# led_stripe_pwm.net
KiCad netlist of a schematic drawn in EAGLE
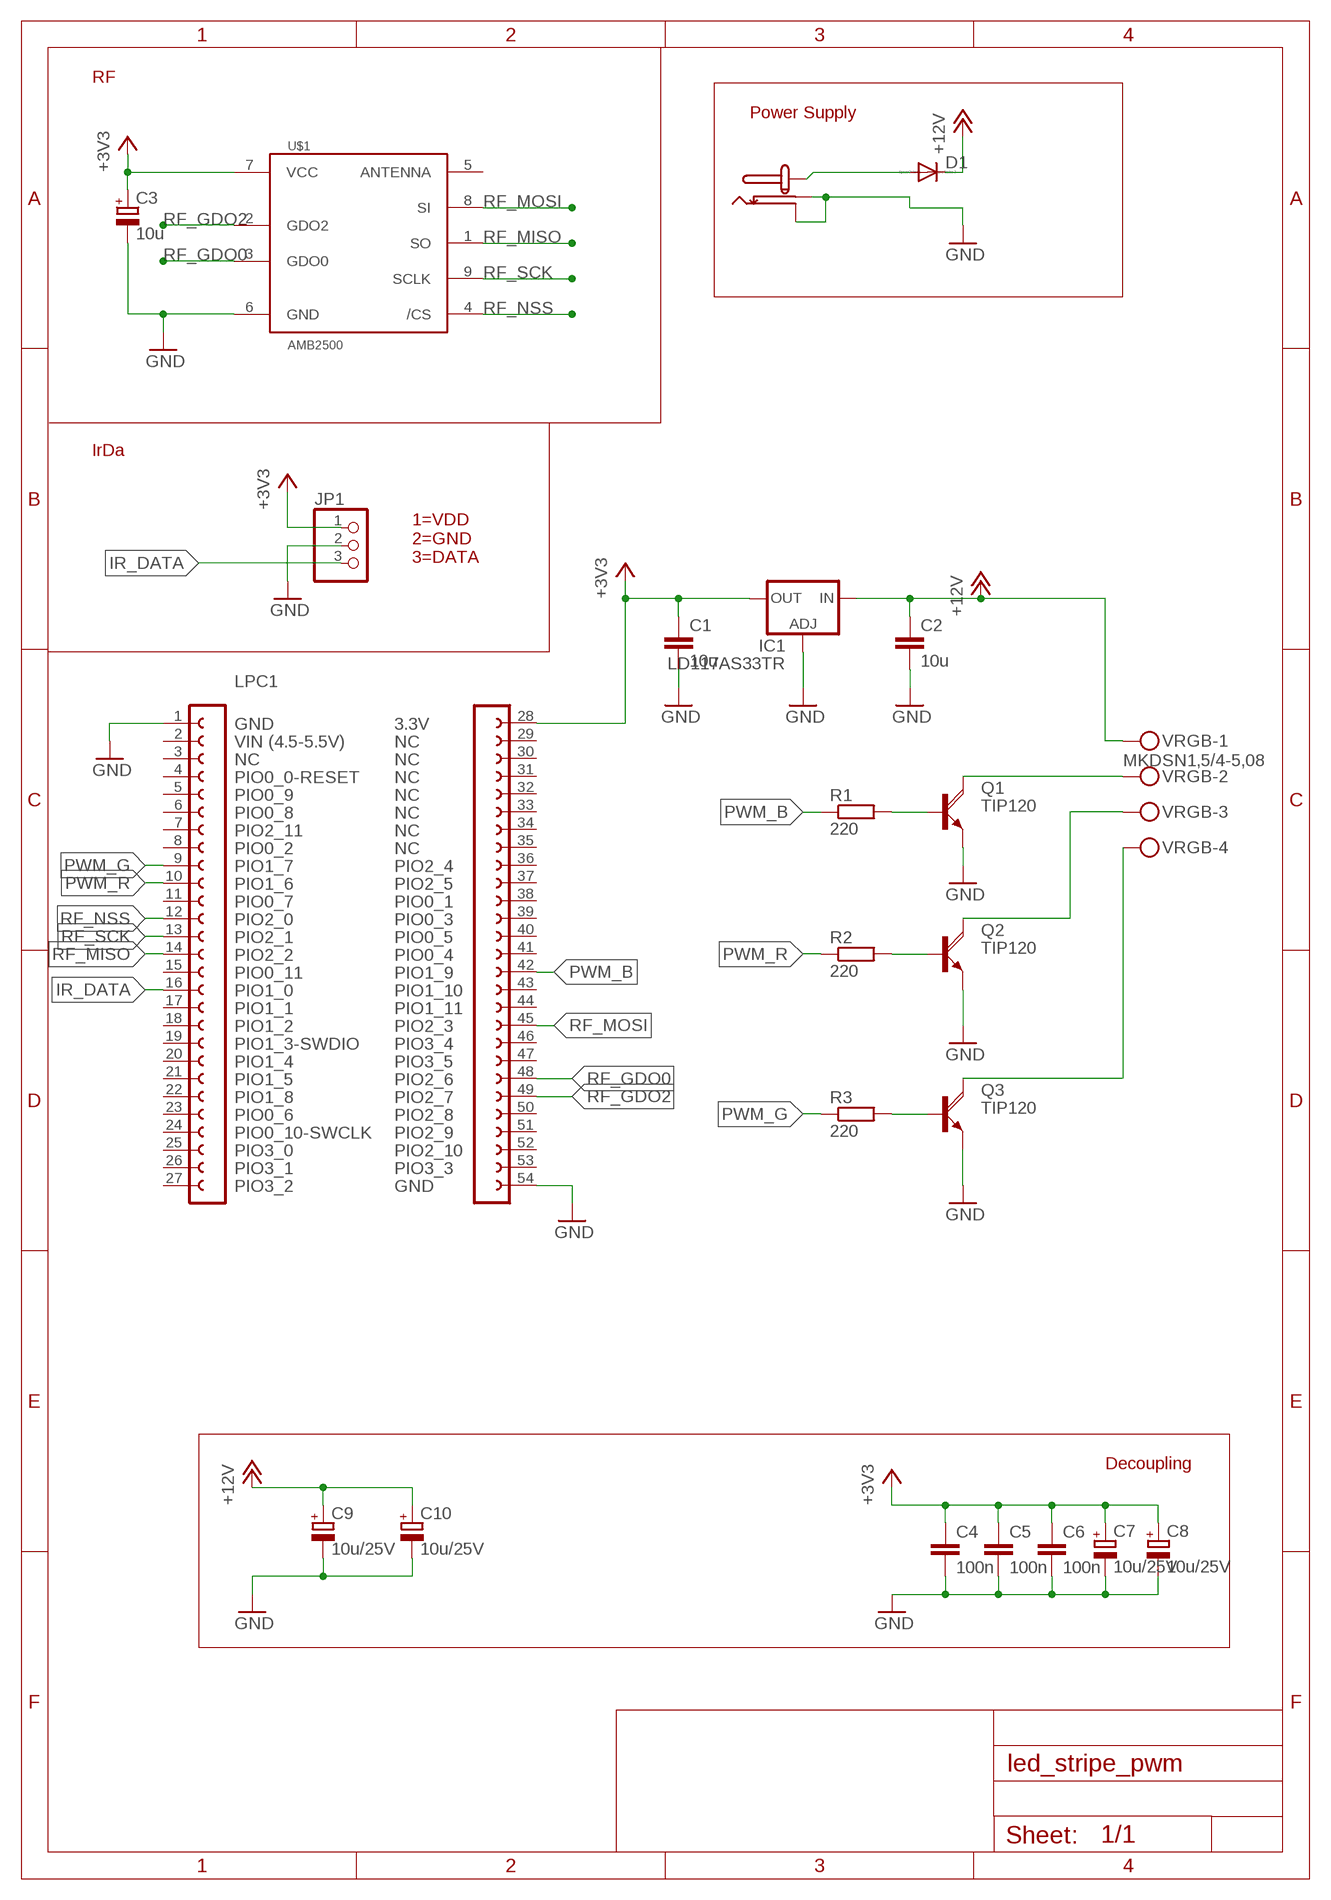
[diagram p0: schematic, sheet 1]

(export (version "E")
  (design (tool "Eeschema 10.0.6"))
  (components
    (comp (ref "C1")
      (value "10u")
      (footprint "eagle-import:C0805K")
      (libsource (lib "eagle-import") (part "C-EUC0805K"))
    )
    (comp (ref "C2")
      (value "10u")
      (footprint "eagle-import:C0805K")
      (libsource (lib "eagle-import") (part "C-EUC0805K"))
    )
    (comp (ref "C3")
      (value "10u")
      (footprint "eagle-import:A_3216-18W")
      (libsource (lib "eagle-import") (part "CPOL-EUA/3216-18W"))
    )
    (comp (ref "C4")
      (value "100n")
      (footprint "eagle-import:C0805")
      (libsource (lib "eagle-import") (part "C-EUC0805"))
    )
    (comp (ref "C5")
      (value "100n")
      (footprint "eagle-import:C0805")
      (libsource (lib "eagle-import") (part "C-EUC0805"))
    )
    (comp (ref "C6")
      (value "100n")
      (footprint "eagle-import:C0805")
      (libsource (lib "eagle-import") (part "C-EUC0805"))
    )
    (comp (ref "C7")
      (value "10u/25V")
      (footprint "eagle-import:PANASONIC_B")
      (libsource (lib "eagle-import") (part "CPOL-EUB"))
    )
    (comp (ref "C8")
      (value "10u/25V")
      (footprint "eagle-import:PANASONIC_B")
      (libsource (lib "eagle-import") (part "CPOL-EUB"))
    )
    (comp (ref "C9")
      (value "10u/25V")
      (footprint "eagle-import:PANASONIC_B")
      (libsource (lib "eagle-import") (part "CPOL-EUB"))
    )
    (comp (ref "C10")
      (value "10u/25V")
      (footprint "eagle-import:PANASONIC_B")
      (libsource (lib "eagle-import") (part "CPOL-EUB"))
    )
    (comp (ref "D1")
      (value "DIODE-DO201-15")
      (footprint "eagle-import:DO201-15")
      (libsource (lib "eagle-import") (part "DIODE-DO201-15"))
    )
    (comp (ref "IC1")
      (value "LD117AS33TR")
      (footprint "eagle-import:SOT223")
      (libsource (lib "eagle-import") (part "LD117A?S33TR"))
    )
    (comp (ref "JP1")
      (value "PINHD-1X3")
      (footprint "eagle-import:1X03")
      (libsource (lib "eagle-import") (part "PINHD-1X3"))
    )
    (comp (ref "LPC1")
      (value "LPCXPRESSO_LPC1114")
      (footprint "eagle-import:LPCXPRESSO_LPC1114")
      (libsource (lib "eagle-import") (part "LPCXPRESSO_LPC1114"))
    )
    (comp (ref "Q1")
      (value "TIP120")
      (footprint "eagle-import:TO220AH")
      (libsource (lib "eagle-import") (part "TIP120"))
    )
    (comp (ref "Q2")
      (value "TIP120")
      (footprint "eagle-import:TO220AH")
      (libsource (lib "eagle-import") (part "TIP120"))
    )
    (comp (ref "Q3")
      (value "TIP120")
      (footprint "eagle-import:TO220AH")
      (libsource (lib "eagle-import") (part "TIP120"))
    )
    (comp (ref "R1")
      (value "220")
      (footprint "eagle-import:R0805")
      (libsource (lib "eagle-import") (part "R-EU_R0805"))
    )
    (comp (ref "R2")
      (value "220")
      (footprint "eagle-import:R0805")
      (libsource (lib "eagle-import") (part "R-EU_R0805"))
    )
    (comp (ref "R3")
      (value "220")
      (footprint "eagle-import:R0805")
      (libsource (lib "eagle-import") (part "R-EU_R0805"))
    )
    (comp (ref "U$1")
      (value "AMB2500")
      (footprint "eagle-import:AMB8400")
      (libsource (lib "eagle-import") (part "AMB8400"))
    )
    (comp (ref "U$2")
      (value "DC_JACK")
      (footprint "eagle-import:DC_JACK_21")
      (libsource (lib "eagle-import") (part "DC_JACK"))
    )
    (comp (ref "VRGB")
      (value "MKDSN1,5/4-5,08")
      (footprint "eagle-import:MKDSN1,5_4-5,08")
      (libsource (lib "eagle-import") (part "MKDSN1,5/4-5,08"))
    )
  )
  (nets
    (net (code "1") (name "+3V3") (class "Default")
      (node (ref "C1") (pin "1") (pinfunction "1_1") (pintype "passive"))
      (node (ref "C3") (pin "+") (pinfunction "+_+") (pintype "passive"))
      (node (ref "C4") (pin "1") (pinfunction "1_1") (pintype "passive"))
      (node (ref "C5") (pin "1") (pinfunction "1_1") (pintype "passive"))
      (node (ref "C6") (pin "1") (pinfunction "1_1") (pintype "passive"))
      (node (ref "C7") (pin "+") (pinfunction "+_+") (pintype "passive"))
      (node (ref "C8") (pin "+") (pinfunction "+_+") (pintype "passive"))
      (node (ref "IC1") (pin "4") (pinfunction "OUT_4") (pintype "passive"))
      (node (ref "JP1") (pin "1") (pinfunction "1_1") (pintype "passive"))
      (node (ref "LPC1") (pin "28") (pinfunction "28_28") (pintype "passive"))
      (node (ref "U$1") (pin "7") (pinfunction "VCC_7") (pintype "power_in"))
    )
    (net (code "2") (name "+12V") (class "Default")
      (node (ref "C10") (pin "+") (pinfunction "+_+") (pintype "passive"))
      (node (ref "C2") (pin "1") (pinfunction "1_1") (pintype "passive"))
      (node (ref "C9") (pin "+") (pinfunction "+_+") (pintype "passive"))
      (node (ref "D1") (pin "C") (pinfunction "C_C") (pintype "passive"))
      (node (ref "IC1") (pin "3") (pinfunction "IN_3") (pintype "input"))
      (node (ref "VRGB") (pin "1") (pinfunction "KL_1") (pintype "passive"))
    )
    (net (code "3") (name "GND") (class "Default")
      (node (ref "C1") (pin "2") (pinfunction "2_2") (pintype "passive"))
      (node (ref "C10") (pin "-") (pinfunction "-_-") (pintype "passive"))
      (node (ref "C2") (pin "2") (pinfunction "2_2") (pintype "passive"))
      (node (ref "C3") (pin "-") (pinfunction "-_-") (pintype "passive"))
      (node (ref "C4") (pin "2") (pinfunction "2_2") (pintype "passive"))
      (node (ref "C5") (pin "2") (pinfunction "2_2") (pintype "passive"))
      (node (ref "C6") (pin "2") (pinfunction "2_2") (pintype "passive"))
      (node (ref "C7") (pin "-") (pinfunction "-_-") (pintype "passive"))
      (node (ref "C8") (pin "-") (pinfunction "-_-") (pintype "passive"))
      (node (ref "C9") (pin "-") (pinfunction "-_-") (pintype "passive"))
      (node (ref "IC1") (pin "1") (pinfunction "ADJ_1") (pintype "input"))
      (node (ref "JP1") (pin "2") (pinfunction "2_2") (pintype "passive"))
      (node (ref "LPC1") (pin "1") (pinfunction "1_1") (pintype "passive"))
      (node (ref "LPC1") (pin "54") (pinfunction "54_54") (pintype "passive"))
      (node (ref "Q1") (pin "E") (pinfunction "E_E") (pintype "passive"))
      (node (ref "Q2") (pin "E") (pinfunction "E_E") (pintype "passive"))
      (node (ref "Q3") (pin "E") (pinfunction "E_E") (pintype "passive"))
      (node (ref "U$1") (pin "6") (pinfunction "GND_6") (pintype "power_in"))
      (node (ref "U$2") (pin "P$2") (pinfunction "P$2_P$2") (pintype "power_in"))
      (node (ref "U$2") (pin "P$3") (pinfunction "P$3_P$3") (pintype "power_in"))
    )
    (net (code "4") (name "IR_DATA") (class "Default")
      (node (ref "JP1") (pin "3") (pinfunction "3_3") (pintype "passive"))
      (node (ref "LPC1") (pin "16") (pinfunction "16_16") (pintype "passive"))
    )
    (net (code "5") (name "Net-(D1-PadA)") (class "Default")
      (node (ref "D1") (pin "A") (pinfunction "A_A") (pintype "passive"))
      (node (ref "U$2") (pin "P$1") (pinfunction "P$1_P$1") (pintype "power_in"))
    )
    (net (code "6") (name "Net-(Q1-PadB)") (class "Default")
      (node (ref "Q1") (pin "B") (pinfunction "B_B") (pintype "passive"))
      (node (ref "R1") (pin "2") (pinfunction "2_2") (pintype "passive"))
    )
    (net (code "7") (name "Net-(Q2-PadB)") (class "Default")
      (node (ref "Q2") (pin "B") (pinfunction "B_B") (pintype "passive"))
      (node (ref "R2") (pin "2") (pinfunction "2_2") (pintype "passive"))
    )
    (net (code "8") (name "Net-(Q3-PadB)") (class "Default")
      (node (ref "Q3") (pin "B") (pinfunction "B_B") (pintype "passive"))
      (node (ref "R3") (pin "2") (pinfunction "2_2") (pintype "passive"))
    )
    (net (code "9") (name "Net-(VRGBB-KL)") (class "Default")
      (node (ref "Q1") (pin "C") (pinfunction "C_C") (pintype "passive"))
      (node (ref "VRGB") (pin "2") (pinfunction "KL_2") (pintype "passive"))
    )
    (net (code "10") (name "Net-(VRGBC-KL)") (class "Default")
      (node (ref "Q2") (pin "C") (pinfunction "C_C") (pintype "passive"))
      (node (ref "VRGB") (pin "3") (pinfunction "KL_3") (pintype "passive"))
    )
    (net (code "11") (name "Net-(VRGBD-KL)") (class "Default")
      (node (ref "Q3") (pin "C") (pinfunction "C_C") (pintype "passive"))
      (node (ref "VRGB") (pin "4") (pinfunction "KL_4") (pintype "passive"))
    )
    (net (code "12") (name "PWM_B") (class "Default")
      (node (ref "LPC1") (pin "42") (pinfunction "42_42") (pintype "passive"))
      (node (ref "R1") (pin "1") (pinfunction "1_1") (pintype "passive"))
    )
    (net (code "13") (name "PWM_G") (class "Default")
      (node (ref "LPC1") (pin "9") (pinfunction "9_9") (pintype "passive"))
      (node (ref "R3") (pin "1") (pinfunction "1_1") (pintype "passive"))
    )
    (net (code "14") (name "PWM_R") (class "Default")
      (node (ref "LPC1") (pin "10") (pinfunction "10_10") (pintype "passive"))
      (node (ref "R2") (pin "1") (pinfunction "1_1") (pintype "passive"))
    )
    (net (code "15") (name "RF_GDO0") (class "Default")
      (node (ref "LPC1") (pin "48") (pinfunction "48_48") (pintype "passive"))
      (node (ref "U$1") (pin "3") (pinfunction "GDO0_3") (pintype "output"))
    )
    (net (code "16") (name "RF_GDO2") (class "Default")
      (node (ref "LPC1") (pin "49") (pinfunction "49_49") (pintype "passive"))
      (node (ref "U$1") (pin "2") (pinfunction "GDO2_2") (pintype "output"))
    )
    (net (code "17") (name "RF_MISO") (class "Default")
      (node (ref "LPC1") (pin "14") (pinfunction "14_14") (pintype "passive"))
      (node (ref "U$1") (pin "1") (pinfunction "SO_1") (pintype "output"))
    )
    (net (code "18") (name "RF_MOSI") (class "Default")
      (node (ref "LPC1") (pin "45") (pinfunction "45_45") (pintype "passive"))
      (node (ref "U$1") (pin "8") (pinfunction "SI_8") (pintype "input"))
    )
    (net (code "19") (name "RF_NSS") (class "Default")
      (node (ref "LPC1") (pin "12") (pinfunction "12_12") (pintype "passive"))
      (node (ref "U$1") (pin "4") (pinfunction "/CS_4") (pintype "input"))
    )
    (net (code "20") (name "RF_SCK") (class "Default")
      (node (ref "LPC1") (pin "13") (pinfunction "13_13") (pintype "passive"))
      (node (ref "U$1") (pin "9") (pinfunction "SCLK_9") (pintype "input"))
    )
    (net (code "21") (name "unconnected-(LPC1-Pad2)") (class "Default")
      (node (ref "LPC1") (pin "2") (pinfunction "2_2") (pintype "passive"))
    )
    (net (code "22") (name "unconnected-(LPC1-Pad3)") (class "Default")
      (node (ref "LPC1") (pin "3") (pinfunction "3_3") (pintype "passive"))
    )
    (net (code "23") (name "unconnected-(LPC1-Pad4)") (class "Default")
      (node (ref "LPC1") (pin "4") (pinfunction "4_4") (pintype "passive"))
    )
    (net (code "24") (name "unconnected-(LPC1-Pad5)") (class "Default")
      (node (ref "LPC1") (pin "5") (pinfunction "5_5") (pintype "passive"))
    )
    (net (code "25") (name "unconnected-(LPC1-Pad6)") (class "Default")
      (node (ref "LPC1") (pin "6") (pinfunction "6_6") (pintype "passive"))
    )
    (net (code "26") (name "unconnected-(LPC1-Pad7)") (class "Default")
      (node (ref "LPC1") (pin "7") (pinfunction "7_7") (pintype "passive"))
    )
    (net (code "27") (name "unconnected-(LPC1-Pad8)") (class "Default")
      (node (ref "LPC1") (pin "8") (pinfunction "8_8") (pintype "passive"))
    )
    (net (code "28") (name "unconnected-(LPC1-Pad11)") (class "Default")
      (node (ref "LPC1") (pin "11") (pinfunction "11_11") (pintype "passive"))
    )
    (net (code "29") (name "unconnected-(LPC1-Pad15)") (class "Default")
      (node (ref "LPC1") (pin "15") (pinfunction "15_15") (pintype "passive"))
    )
    (net (code "30") (name "unconnected-(LPC1-Pad17)") (class "Default")
      (node (ref "LPC1") (pin "17") (pinfunction "17_17") (pintype "passive"))
    )
    (net (code "31") (name "unconnected-(LPC1-Pad18)") (class "Default")
      (node (ref "LPC1") (pin "18") (pinfunction "18_18") (pintype "passive"))
    )
    (net (code "32") (name "unconnected-(LPC1-Pad19)") (class "Default")
      (node (ref "LPC1") (pin "19") (pinfunction "19_19") (pintype "passive"))
    )
    (net (code "33") (name "unconnected-(LPC1-Pad20)") (class "Default")
      (node (ref "LPC1") (pin "20") (pinfunction "20_20") (pintype "passive"))
    )
    (net (code "34") (name "unconnected-(LPC1-Pad21)") (class "Default")
      (node (ref "LPC1") (pin "21") (pinfunction "21_21") (pintype "passive"))
    )
    (net (code "35") (name "unconnected-(LPC1-Pad22)") (class "Default")
      (node (ref "LPC1") (pin "22") (pinfunction "22_22") (pintype "passive"))
    )
    (net (code "36") (name "unconnected-(LPC1-Pad23)") (class "Default")
      (node (ref "LPC1") (pin "23") (pinfunction "23_23") (pintype "passive"))
    )
    (net (code "37") (name "unconnected-(LPC1-Pad24)") (class "Default")
      (node (ref "LPC1") (pin "24") (pinfunction "24_24") (pintype "passive"))
    )
    (net (code "38") (name "unconnected-(LPC1-Pad25)") (class "Default")
      (node (ref "LPC1") (pin "25") (pinfunction "25_25") (pintype "passive"))
    )
    (net (code "39") (name "unconnected-(LPC1-Pad26)") (class "Default")
      (node (ref "LPC1") (pin "26") (pinfunction "26_26") (pintype "passive"))
    )
    (net (code "40") (name "unconnected-(LPC1-Pad27)") (class "Default")
      (node (ref "LPC1") (pin "27") (pinfunction "27_27") (pintype "passive"))
    )
    (net (code "41") (name "unconnected-(LPC1-Pad29)") (class "Default")
      (node (ref "LPC1") (pin "29") (pinfunction "29_29") (pintype "passive"))
    )
    (net (code "42") (name "unconnected-(LPC1-Pad30)") (class "Default")
      (node (ref "LPC1") (pin "30") (pinfunction "30_30") (pintype "passive"))
    )
    (net (code "43") (name "unconnected-(LPC1-Pad31)") (class "Default")
      (node (ref "LPC1") (pin "31") (pinfunction "31_31") (pintype "passive"))
    )
    (net (code "44") (name "unconnected-(LPC1-Pad32)") (class "Default")
      (node (ref "LPC1") (pin "32") (pinfunction "32_32") (pintype "passive"))
    )
    (net (code "45") (name "unconnected-(LPC1-Pad33)") (class "Default")
      (node (ref "LPC1") (pin "33") (pinfunction "33_33") (pintype "passive"))
    )
    (net (code "46") (name "unconnected-(LPC1-Pad34)") (class "Default")
      (node (ref "LPC1") (pin "34") (pinfunction "34_34") (pintype "passive"))
    )
    (net (code "47") (name "unconnected-(LPC1-Pad35)") (class "Default")
      (node (ref "LPC1") (pin "35") (pinfunction "35_35") (pintype "passive"))
    )
    (net (code "48") (name "unconnected-(LPC1-Pad36)") (class "Default")
      (node (ref "LPC1") (pin "36") (pinfunction "36_36") (pintype "passive"))
    )
    (net (code "49") (name "unconnected-(LPC1-Pad37)") (class "Default")
      (node (ref "LPC1") (pin "37") (pinfunction "37_37") (pintype "passive"))
    )
    (net (code "50") (name "unconnected-(LPC1-Pad38)") (class "Default")
      (node (ref "LPC1") (pin "38") (pinfunction "38_38") (pintype "passive"))
    )
    (net (code "51") (name "unconnected-(LPC1-Pad39)") (class "Default")
      (node (ref "LPC1") (pin "39") (pinfunction "39_39") (pintype "passive"))
    )
    (net (code "52") (name "unconnected-(LPC1-Pad40)") (class "Default")
      (node (ref "LPC1") (pin "40") (pinfunction "40_40") (pintype "passive"))
    )
    (net (code "53") (name "unconnected-(LPC1-Pad41)") (class "Default")
      (node (ref "LPC1") (pin "41") (pinfunction "41_41") (pintype "passive"))
    )
    (net (code "54") (name "unconnected-(LPC1-Pad43)") (class "Default")
      (node (ref "LPC1") (pin "43") (pinfunction "43_43") (pintype "passive"))
    )
    (net (code "55") (name "unconnected-(LPC1-Pad44)") (class "Default")
      (node (ref "LPC1") (pin "44") (pinfunction "44_44") (pintype "passive"))
    )
    (net (code "56") (name "unconnected-(LPC1-Pad46)") (class "Default")
      (node (ref "LPC1") (pin "46") (pinfunction "46_46") (pintype "passive"))
    )
    (net (code "57") (name "unconnected-(LPC1-Pad47)") (class "Default")
      (node (ref "LPC1") (pin "47") (pinfunction "47_47") (pintype "passive"))
    )
    (net (code "58") (name "unconnected-(LPC1-Pad50)") (class "Default")
      (node (ref "LPC1") (pin "50") (pinfunction "50_50") (pintype "passive"))
    )
    (net (code "59") (name "unconnected-(LPC1-Pad51)") (class "Default")
      (node (ref "LPC1") (pin "51") (pinfunction "51_51") (pintype "passive"))
    )
    (net (code "60") (name "unconnected-(LPC1-Pad52)") (class "Default")
      (node (ref "LPC1") (pin "52") (pinfunction "52_52") (pintype "passive"))
    )
    (net (code "61") (name "unconnected-(LPC1-Pad53)") (class "Default")
      (node (ref "LPC1") (pin "53") (pinfunction "53_53") (pintype "passive"))
    )
    (net (code "62") (name "unconnected-(U$1-ANTENNA-Pad5)") (class "Default")
      (node (ref "U$1") (pin "5") (pinfunction "ANTENNA_5") (pintype "output"))
    )
  )
)
